# MCU_144_IOs.net
KiCad netlist of a schematic drawn in Altium Designer
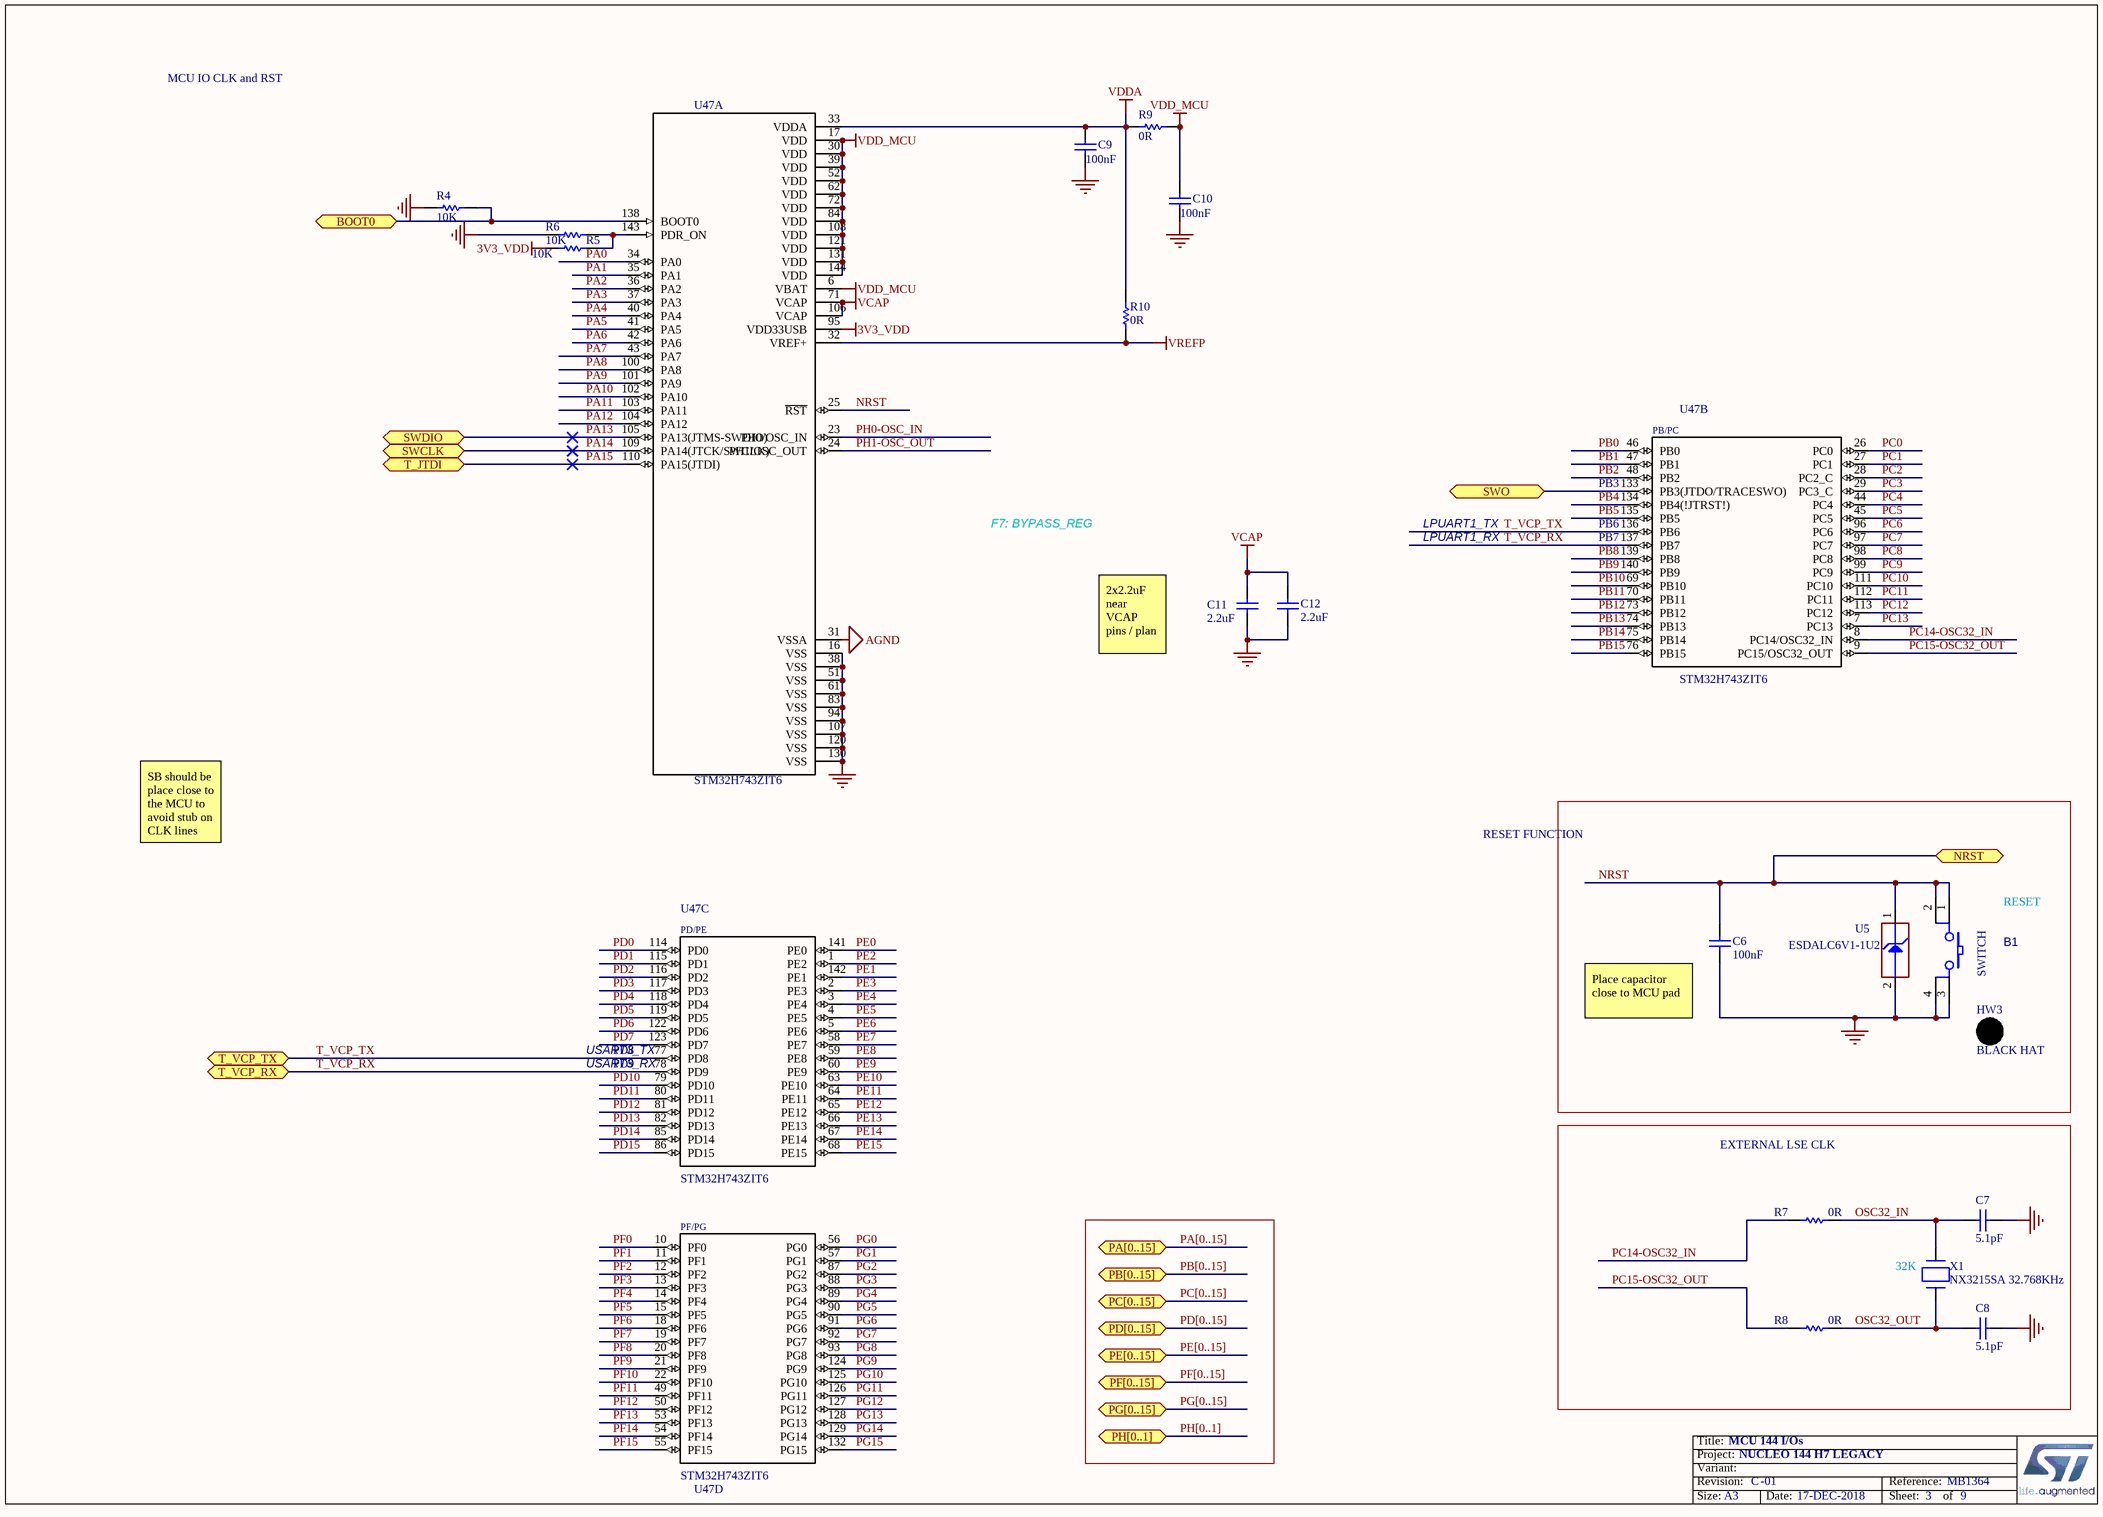
[diagram p0: MCU_144_IOs.SchDoc]

(export (version "E")
  (design (tool "Eeschema 10.0.6"))
  (components
    (comp (ref "B1")
      (value "SWITCH")
      (footprint "SWI_WEALTHMETAL_TD-0341_4P_BLACK")
      (description "Non-Open Push-Button 0.1A 24V BLACK")
      (fields
        (field (name "INTERNAL_PART_NUMBER") "MCD-00001")
        (field (name "MANUFACTURER_PART_NUMBER") "TD-0341")
        (field (name "PROVIDED_BY") "SUBCO")
      )
      (libsource (lib "MCD_PARTS_database") (part "SW-PUSH-CMS"))
    )
    (comp (ref "C6")
      (value "100nF")
      (footprint "C0603")
      (description "Capacitor, MLCC, 100nF, 6V3, X5R, 10%, 0603, T=0,8mm")
      (fields
        (field (name "INTERNAL_PART_NUMBER") "MCD-00237")
        (field (name "MANUFACTURER_PART_NUMBER") "CC0603KRX5R5BB104")
        (field (name "PROVIDED_BY") "SUBCO")
      )
      (libsource (lib "MCD_PARTS_database") (part "Capacitor"))
    )
    (comp (ref "C7")
      (value "5.1pF")
      (footprint "C0402")
      (description "Capacitor, MLCC, 5.1pF, 50V, NPO, +-0.25pF, 0402, T=0.5mm")
      (fields
        (field (name "INTERNAL_PART_NUMBER") "MCD-00003")
        (field (name "MANUFACTURER_PART_NUMBER") "CC0402CRNPO9BN5R1")
        (field (name "PROVIDED_BY") "SUBCO")
      )
      (libsource (lib "MCD_PARTS_database") (part "Capacitor"))
    )
    (comp (ref "C8")
      (value "5.1pF")
      (footprint "C0402")
      (description "Capacitor, MLCC, 5.1pF, 50V, NPO, +-0.25pF, 0402, T=0.5mm")
      (fields
        (field (name "INTERNAL_PART_NUMBER") "MCD-00003")
        (field (name "MANUFACTURER_PART_NUMBER") "CC0402CRNPO9BN5R1")
        (field (name "PROVIDED_BY") "SUBCO")
      )
      (libsource (lib "MCD_PARTS_database") (part "Capacitor"))
    )
    (comp (ref "C9")
      (value "Capacitor")
      (footprint "C0402")
      (description "CAP CER 0.1UF 16V X7R 0402")
      (fields
        (field (name "MANUFACTURER") "Yageo")
        (field (name "MANUFACTURER PART NUMBER") "CC0402KRX7R7BB104")
        (field (name "CAPACITANCE") "100nF")
      )
      (libsource (lib "MCD_PARTS_database") (part "Capacitor"))
    )
    (comp (ref "C10")
      (value "Capacitor")
      (footprint "C0402")
      (description "CAP CER 0.1UF 16V X7R 0402")
      (fields
        (field (name "MANUFACTURER") "Yageo")
        (field (name "MANUFACTURER PART NUMBER") "CC0402KRX7R7BB104")
        (field (name "CAPACITANCE") "100nF")
      )
      (libsource (lib "MCD_PARTS_database") (part "Capacitor"))
    )
    (comp (ref "C11")
      (value "2.2uF")
      (footprint "C0603")
      (description "Capacitor, MLCC, 2.2uF, 10V, X5R, 10%, 0603, T=0,8mm")
      (fields
        (field (name "INTERNAL_PART_NUMBER") "MCD-00012")
        (field (name "MANUFACTURER_PART_NUMBER") "CC0603KRX5R6BB225")
        (field (name "PROVIDED_BY") "SUBCO")
      )
      (libsource (lib "MCD_PARTS_database") (part "Capacitor"))
    )
    (comp (ref "C12")
      (value "2.2uF")
      (footprint "C0603")
      (description "Capacitor, MLCC, 2.2uF, 10V, X5R, 10%, 0603, T=0,8mm")
      (fields
        (field (name "INTERNAL_PART_NUMBER") "MCD-00012")
        (field (name "MANUFACTURER_PART_NUMBER") "CC0603KRX5R6BB225")
        (field (name "PROVIDED_BY") "SUBCO")
      )
      (libsource (lib "MCD_PARTS_database") (part "Capacitor"))
    )
    (comp (ref "HW3")
      (value "BLACK HAT")
      (description "Black Hat for switch TD0341X-G01-BLA")
      (fields
        (field (name "INTERNAL_PART_NUMBER") "MCD-00635")
        (field (name "MANUFACTURER_PART_NUMBER") "988.16.09.3.00003_SH-517")
        (field (name "PROVIDED_BY") "SUBCO")
      )
      (libsource (lib "MCD_PARTS_database") (part "BUTTON_HAT_BLACK"))
    )
    (comp (ref "R4")
      (value "10K")
      (footprint "R0603")
      (description "Resistor,10K,0603,1%,1/10W")
      (fields
        (field (name "INTERNAL_PART_NUMBER") "MCD-00220")
        (field (name "MANUFACTURER_PART_NUMBER") "RC0603FR-0710KL")
        (field (name "PROVIDED_BY") "SUBCO")
      )
      (libsource (lib "MCD_PARTS_database") (part "Resistor"))
    )
    (comp (ref "R5")
      (value "10K")
      (footprint "R0603")
      (description "Resistor,10K,0603,1%,1/10W")
      (fields
        (field (name "INTERNAL_PART_NUMBER") "MCD-00220")
        (field (name "MANUFACTURER_PART_NUMBER") "RC0603FR-0710KL")
        (field (name "PROVIDED_BY") "SUBCO")
      )
      (libsource (lib "MCD_PARTS_database") (part "Resistor"))
    )
    (comp (ref "R6")
      (value "10K")
      (footprint "R0603")
      (description "Resistor,10K,0603,1%,1/10W")
      (fields
        (field (name "INTERNAL_PART_NUMBER") "MCD-00220")
        (field (name "MANUFACTURER_PART_NUMBER") "RC0603FR-0710KL")
        (field (name "PROVIDED_BY") "SUBCO")
      )
      (libsource (lib "MCD_PARTS_database") (part "Resistor"))
    )
    (comp (ref "R7")
      (value "0R")
      (footprint "R0603")
      (description "Resistor,0R,0603,5%,1/10W")
      (fields
        (field (name "INTERNAL_PART_NUMBER") "MCD-00056")
        (field (name "MANUFACTURER_PART_NUMBER") "RC0603JR-070RL")
        (field (name "PROVIDED_BY") "SUBCO")
      )
      (libsource (lib "MCD_PARTS_database") (part "Resistor"))
    )
    (comp (ref "R8")
      (value "0R")
      (footprint "R0603")
      (description "Resistor,0R,0603,5%,1/10W")
      (fields
        (field (name "INTERNAL_PART_NUMBER") "MCD-00056")
        (field (name "MANUFACTURER_PART_NUMBER") "RC0603JR-070RL")
        (field (name "PROVIDED_BY") "SUBCO")
      )
      (libsource (lib "MCD_PARTS_database") (part "Resistor"))
    )
    (comp (ref "R9")
      (value "0R")
      (footprint "R0603")
      (description "Resistor,0R,0603,5%,1/10W")
      (fields
        (field (name "INTERNAL_PART_NUMBER") "MCD-00056")
        (field (name "MANUFACTURER_PART_NUMBER") "RC0603JR-070RL")
        (field (name "PROVIDED_BY") "SUBCO")
      )
      (libsource (lib "MCD_PARTS_database") (part "Resistor"))
    )
    (comp (ref "R10")
      (value "0R")
      (footprint "R0603")
      (description "Resistor,0R,0603,5%,1/10W")
      (fields
        (field (name "INTERNAL_PART_NUMBER") "MCD-00056")
        (field (name "MANUFACTURER_PART_NUMBER") "RC0603JR-070RL")
        (field (name "PROVIDED_BY") "SUBCO")
      )
      (libsource (lib "MCD_PARTS_database") (part "Resistor"))
    )
    (comp (ref "U5")
      (value "ESDALC6V1-1U2")
      (footprint "ESD_ST0201")
      (description "ESD protection 6V1")
      (fields
        (field (name "INTERNAL_PART_NUMBER") "MCD-00170")
        (field (name "MANUFACTURER") "STMICROELECTRONICS")
        (field (name "PROVIDED_BY") "SUBCO with ST control")
      )
      (libsource (lib "MCD_PARTS_database") (part "ESD-TRANSIL"))
    )
    (comp (ref "U47")
      (value "STM32H743ZIT6")
      (footprint "*QFP50P2200X2200X160-144N")
      (fields (field (name "MF") "STMicroelectronics") (field (name "DIGI-KEY_PART_NUMBER") "497-17721-ND"))
      (libsource (lib "STM32H743ZIT6") (part "STM32H743ZIT6"))
    )
    (comp (ref "X1")
      (value "NX3215SA 32.768KHz")
      (footprint "CRY_NX3215SA_2P")
      (description "Crystal 32.768kHz, 6pF, +-20ppm, 50Kohms max, SMD")
      (fields
        (field (name "INTERNAL_PART_NUMBER") "MCD-00091")
        (field (name "MANUFACTURER_PART_NUMBER") "NX3215SA 32.768KHz EXS00A-MU00525")
        (field (name "PROVIDED_BY") "SUBCO")
      )
      (libsource (lib "MCD_PARTS_database") (part "XTAL_2_PINS"))
    )
  )
  (nets
    (net (code "10") (name "/BOOT0") (class "Default")
      (node (ref "R4") (pin "1") (pinfunction "1_1") (pintype "passive"))
      (node (ref "U47") (pin "138") (pinfunction "BOOT0_138") (pintype "input"))
    )
    (net (code "11") (name "/NRST") (class "Default")
      (node (ref "B1") (pin "1") (pinfunction "1_1") (pintype "passive"))
      (node (ref "B1") (pin "2") (pinfunction "2_2") (pintype "passive"))
      (node (ref "C6") (pin "2") (pinfunction "2_2") (pintype "passive"))
      (node (ref "U47") (pin "25") (pinfunction "~{RST}_25") (pintype "bidirectional"))
      (node (ref "U5") (pin "1") (pinfunction "IO1_1") (pintype "passive"))
    )
    (net (code "12") (name "/OSC32_IN") (class "Default")
      (node (ref "C7") (pin "1") (pinfunction "1_1") (pintype "passive"))
      (node (ref "R7") (pin "2") (pinfunction "2_2") (pintype "passive"))
      (node (ref "X1") (pin "2") (pinfunction "X2_2") (pintype "passive"))
    )
    (net (code "13") (name "/OSC32_OUT") (class "Default")
      (node (ref "C8") (pin "1") (pinfunction "1_1") (pintype "passive"))
      (node (ref "R8") (pin "2") (pinfunction "2_2") (pintype "passive"))
      (node (ref "X1") (pin "1") (pinfunction "X1_1") (pintype "passive"))
    )
    (net (code "14") (name "/PA0") (class "Default")
      (node (ref "U47") (pin "34") (pinfunction "PA0_34") (pintype "bidirectional"))
    )
    (net (code "15") (name "/PA1") (class "Default")
      (node (ref "U47") (pin "35") (pinfunction "PA1_35") (pintype "bidirectional"))
    )
    (net (code "16") (name "/PA2") (class "Default")
      (node (ref "U47") (pin "36") (pinfunction "PA2_36") (pintype "bidirectional"))
    )
    (net (code "17") (name "/PA3") (class "Default")
      (node (ref "U47") (pin "37") (pinfunction "PA3_37") (pintype "bidirectional"))
    )
    (net (code "18") (name "/PA4") (class "Default")
      (node (ref "U47") (pin "40") (pinfunction "PA4_40") (pintype "bidirectional"))
    )
    (net (code "19") (name "/PA5") (class "Default")
      (node (ref "U47") (pin "41") (pinfunction "PA5_41") (pintype "bidirectional"))
    )
    (net (code "20") (name "/PA6") (class "Default")
      (node (ref "U47") (pin "42") (pinfunction "PA6_42") (pintype "bidirectional"))
    )
    (net (code "21") (name "/PA7") (class "Default")
      (node (ref "U47") (pin "43") (pinfunction "PA7_43") (pintype "bidirectional"))
    )
    (net (code "22") (name "/PA8") (class "Default")
      (node (ref "U47") (pin "100") (pinfunction "PA8_100") (pintype "bidirectional"))
    )
    (net (code "23") (name "/PA9") (class "Default")
      (node (ref "U47") (pin "101") (pinfunction "PA9_101") (pintype "bidirectional"))
    )
    (net (code "24") (name "/PA10") (class "Default")
      (node (ref "U47") (pin "102") (pinfunction "PA10_102") (pintype "bidirectional"))
    )
    (net (code "25") (name "/PA11") (class "Default")
      (node (ref "U47") (pin "103") (pinfunction "PA11_103") (pintype "bidirectional"))
    )
    (net (code "26") (name "/PA12") (class "Default")
      (node (ref "U47") (pin "104") (pinfunction "PA12_104") (pintype "bidirectional"))
    )
    (net (code "27") (name "/PA13") (class "Default")
      (node (ref "U47") (pin "105") (pinfunction "PA13(JTMS-SWDIO)_105") (pintype "bidirectional"))
    )
    (net (code "28") (name "/PA14") (class "Default")
      (node (ref "U47") (pin "109") (pinfunction "PA14(JTCK/SWCLK)_109") (pintype "bidirectional"))
    )
    (net (code "29") (name "/PA15") (class "Default")
      (node (ref "U47") (pin "110") (pinfunction "PA15(JTDI)_110") (pintype "bidirectional"))
    )
    (net (code "31") (name "/PB0") (class "Default")
      (node (ref "U47") (pin "46") (pinfunction "PB0_46") (pintype "bidirectional"))
    )
    (net (code "32") (name "/PB1") (class "Default")
      (node (ref "U47") (pin "47") (pinfunction "PB1_47") (pintype "bidirectional"))
    )
    (net (code "33") (name "/PB2") (class "Default")
      (node (ref "U47") (pin "48") (pinfunction "PB2_48") (pintype "bidirectional"))
    )
    (net (code "34") (name "/PB4") (class "Default")
      (node (ref "U47") (pin "134") (pinfunction "PB4(!JTRST!)_134") (pintype "bidirectional"))
    )
    (net (code "35") (name "/PB5") (class "Default")
      (node (ref "U47") (pin "135") (pinfunction "PB5_135") (pintype "bidirectional"))
    )
    (net (code "36") (name "/PB8") (class "Default")
      (node (ref "U47") (pin "139") (pinfunction "PB8_139") (pintype "bidirectional"))
    )
    (net (code "37") (name "/PB9") (class "Default")
      (node (ref "U47") (pin "140") (pinfunction "PB9_140") (pintype "bidirectional"))
    )
    (net (code "38") (name "/PB10") (class "Default")
      (node (ref "U47") (pin "69") (pinfunction "PB10_69") (pintype "bidirectional"))
    )
    (net (code "39") (name "/PB11") (class "Default")
      (node (ref "U47") (pin "70") (pinfunction "PB11_70") (pintype "bidirectional"))
    )
    (net (code "40") (name "/PB12") (class "Default")
      (node (ref "U47") (pin "73") (pinfunction "PB12_73") (pintype "bidirectional"))
    )
    (net (code "41") (name "/PB13") (class "Default")
      (node (ref "U47") (pin "74") (pinfunction "PB13_74") (pintype "bidirectional"))
    )
    (net (code "42") (name "/PB14") (class "Default")
      (node (ref "U47") (pin "75") (pinfunction "PB14_75") (pintype "bidirectional"))
    )
    (net (code "43") (name "/PB15") (class "Default")
      (node (ref "U47") (pin "76") (pinfunction "PB15_76") (pintype "bidirectional"))
    )
    (net (code "45") (name "/PC0") (class "Default")
      (node (ref "U47") (pin "26") (pinfunction "PC0_26") (pintype "bidirectional"))
    )
    (net (code "46") (name "/PC1") (class "Default")
      (node (ref "U47") (pin "27") (pinfunction "PC1_27") (pintype "bidirectional"))
    )
    (net (code "47") (name "/PC2") (class "Default")
      (node (ref "U47") (pin "28") (pinfunction "PC2_C_28") (pintype "bidirectional"))
    )
    (net (code "48") (name "/PC3") (class "Default")
      (node (ref "U47") (pin "29") (pinfunction "PC3_C_29") (pintype "bidirectional"))
    )
    (net (code "49") (name "/PC4") (class "Default")
      (node (ref "U47") (pin "44") (pinfunction "PC4_44") (pintype "bidirectional"))
    )
    (net (code "50") (name "/PC5") (class "Default")
      (node (ref "U47") (pin "45") (pinfunction "PC5_45") (pintype "bidirectional"))
    )
    (net (code "51") (name "/PC6") (class "Default")
      (node (ref "U47") (pin "96") (pinfunction "PC6_96") (pintype "bidirectional"))
    )
    (net (code "52") (name "/PC7") (class "Default")
      (node (ref "U47") (pin "97") (pinfunction "PC7_97") (pintype "bidirectional"))
    )
    (net (code "53") (name "/PC8") (class "Default")
      (node (ref "U47") (pin "98") (pinfunction "PC8_98") (pintype "bidirectional"))
    )
    (net (code "54") (name "/PC9") (class "Default")
      (node (ref "U47") (pin "99") (pinfunction "PC9_99") (pintype "bidirectional"))
    )
    (net (code "55") (name "/PC10") (class "Default")
      (node (ref "U47") (pin "111") (pinfunction "PC10_111") (pintype "bidirectional"))
    )
    (net (code "56") (name "/PC11") (class "Default")
      (node (ref "U47") (pin "112") (pinfunction "PC11_112") (pintype "bidirectional"))
    )
    (net (code "57") (name "/PC12") (class "Default")
      (node (ref "U47") (pin "113") (pinfunction "PC12_113") (pintype "bidirectional"))
    )
    (net (code "58") (name "/PC13") (class "Default")
      (node (ref "U47") (pin "7") (pinfunction "PC13_7") (pintype "bidirectional"))
    )
    (net (code "59") (name "/PC14-OSC32_IN") (class "Default")
      (node (ref "R7") (pin "1") (pinfunction "1_1") (pintype "passive"))
      (node (ref "U47") (pin "8") (pinfunction "PC14/OSC32_IN_8") (pintype "bidirectional"))
    )
    (net (code "60") (name "/PC15-OSC32_OUT") (class "Default")
      (node (ref "R8") (pin "1") (pinfunction "1_1") (pintype "passive"))
      (node (ref "U47") (pin "9") (pinfunction "PC15/OSC32_OUT_9") (pintype "bidirectional"))
    )
    (net (code "62") (name "/PD0") (class "Default")
      (node (ref "U47") (pin "114") (pinfunction "PD0_114") (pintype "bidirectional"))
    )
    (net (code "63") (name "/PD1") (class "Default")
      (node (ref "U47") (pin "115") (pinfunction "PD1_115") (pintype "bidirectional"))
    )
    (net (code "64") (name "/PD2") (class "Default")
      (node (ref "U47") (pin "116") (pinfunction "PD2_116") (pintype "bidirectional"))
    )
    (net (code "65") (name "/PD3") (class "Default")
      (node (ref "U47") (pin "117") (pinfunction "PD3_117") (pintype "bidirectional"))
    )
    (net (code "66") (name "/PD4") (class "Default")
      (node (ref "U47") (pin "118") (pinfunction "PD4_118") (pintype "bidirectional"))
    )
    (net (code "67") (name "/PD5") (class "Default")
      (node (ref "U47") (pin "119") (pinfunction "PD5_119") (pintype "bidirectional"))
    )
    (net (code "68") (name "/PD6") (class "Default")
      (node (ref "U47") (pin "122") (pinfunction "PD6_122") (pintype "bidirectional"))
    )
    (net (code "69") (name "/PD7") (class "Default")
      (node (ref "U47") (pin "123") (pinfunction "PD7_123") (pintype "bidirectional"))
    )
    (net (code "70") (name "/PD10") (class "Default")
      (node (ref "U47") (pin "79") (pinfunction "PD10_79") (pintype "bidirectional"))
    )
    (net (code "71") (name "/PD11") (class "Default")
      (node (ref "U47") (pin "80") (pinfunction "PD11_80") (pintype "bidirectional"))
    )
    (net (code "72") (name "/PD12") (class "Default")
      (node (ref "U47") (pin "81") (pinfunction "PD12_81") (pintype "bidirectional"))
    )
    (net (code "73") (name "/PD13") (class "Default")
      (node (ref "U47") (pin "82") (pinfunction "PD13_82") (pintype "bidirectional"))
    )
    (net (code "74") (name "/PD14") (class "Default")
      (node (ref "U47") (pin "85") (pinfunction "PD14_85") (pintype "bidirectional"))
    )
    (net (code "75") (name "/PD15") (class "Default")
      (node (ref "U47") (pin "86") (pinfunction "PD15_86") (pintype "bidirectional"))
    )
    (net (code "77") (name "/PE0") (class "Default")
      (node (ref "U47") (pin "141") (pinfunction "PE0_141") (pintype "bidirectional"))
    )
    (net (code "78") (name "/PE1") (class "Default")
      (node (ref "U47") (pin "142") (pinfunction "PE1_142") (pintype "bidirectional"))
    )
    (net (code "79") (name "/PE2") (class "Default")
      (node (ref "U47") (pin "1") (pinfunction "PE2_1") (pintype "bidirectional"))
    )
    (net (code "80") (name "/PE3") (class "Default")
      (node (ref "U47") (pin "2") (pinfunction "PE3_2") (pintype "bidirectional"))
    )
    (net (code "81") (name "/PE4") (class "Default")
      (node (ref "U47") (pin "3") (pinfunction "PE4_3") (pintype "bidirectional"))
    )
    (net (code "82") (name "/PE5") (class "Default")
      (node (ref "U47") (pin "4") (pinfunction "PE5_4") (pintype "bidirectional"))
    )
    (net (code "83") (name "/PE6") (class "Default")
      (node (ref "U47") (pin "5") (pinfunction "PE6_5") (pintype "bidirectional"))
    )
    (net (code "84") (name "/PE7") (class "Default")
      (node (ref "U47") (pin "58") (pinfunction "PE7_58") (pintype "bidirectional"))
    )
    (net (code "85") (name "/PE8") (class "Default")
      (node (ref "U47") (pin "59") (pinfunction "PE8_59") (pintype "bidirectional"))
    )
    (net (code "86") (name "/PE9") (class "Default")
      (node (ref "U47") (pin "60") (pinfunction "PE9_60") (pintype "bidirectional"))
    )
    (net (code "87") (name "/PE10") (class "Default")
      (node (ref "U47") (pin "63") (pinfunction "PE10_63") (pintype "bidirectional"))
    )
    (net (code "88") (name "/PE11") (class "Default")
      (node (ref "U47") (pin "64") (pinfunction "PE11_64") (pintype "bidirectional"))
    )
    (net (code "89") (name "/PE12") (class "Default")
      (node (ref "U47") (pin "65") (pinfunction "PE12_65") (pintype "bidirectional"))
    )
    (net (code "90") (name "/PE13") (class "Default")
      (node (ref "U47") (pin "66") (pinfunction "PE13_66") (pintype "bidirectional"))
    )
    (net (code "91") (name "/PE14") (class "Default")
      (node (ref "U47") (pin "67") (pinfunction "PE14_67") (pintype "bidirectional"))
    )
    (net (code "92") (name "/PE15") (class "Default")
      (node (ref "U47") (pin "68") (pinfunction "PE15_68") (pintype "bidirectional"))
    )
    (net (code "94") (name "/PF0") (class "Default")
      (node (ref "U47") (pin "10") (pinfunction "PF0_10") (pintype "bidirectional"))
    )
    (net (code "95") (name "/PF1") (class "Default")
      (node (ref "U47") (pin "11") (pinfunction "PF1_11") (pintype "bidirectional"))
    )
    (net (code "96") (name "/PF2") (class "Default")
      (node (ref "U47") (pin "12") (pinfunction "PF2_12") (pintype "bidirectional"))
    )
    (net (code "97") (name "/PF3") (class "Default")
      (node (ref "U47") (pin "13") (pinfunction "PF3_13") (pintype "bidirectional"))
    )
    (net (code "98") (name "/PF4") (class "Default")
      (node (ref "U47") (pin "14") (pinfunction "PF4_14") (pintype "bidirectional"))
    )
    (net (code "99") (name "/PF5") (class "Default")
      (node (ref "U47") (pin "15") (pinfunction "PF5_15") (pintype "bidirectional"))
    )
    (net (code "100") (name "/PF6") (class "Default")
      (node (ref "U47") (pin "18") (pinfunction "PF6_18") (pintype "bidirectional"))
    )
    (net (code "101") (name "/PF7") (class "Default")
      (node (ref "U47") (pin "19") (pinfunction "PF7_19") (pintype "bidirectional"))
    )
    (net (code "102") (name "/PF8") (class "Default")
      (node (ref "U47") (pin "20") (pinfunction "PF8_20") (pintype "bidirectional"))
    )
    (net (code "103") (name "/PF9") (class "Default")
      (node (ref "U47") (pin "21") (pinfunction "PF9_21") (pintype "bidirectional"))
    )
    (net (code "104") (name "/PF10") (class "Default")
      (node (ref "U47") (pin "22") (pinfunction "PF10_22") (pintype "bidirectional"))
    )
    (net (code "105") (name "/PF11") (class "Default")
      (node (ref "U47") (pin "49") (pinfunction "PF11_49") (pintype "bidirectional"))
    )
    (net (code "106") (name "/PF12") (class "Default")
      (node (ref "U47") (pin "50") (pinfunction "PF12_50") (pintype "bidirectional"))
    )
    (net (code "107") (name "/PF13") (class "Default")
      (node (ref "U47") (pin "53") (pinfunction "PF13_53") (pintype "bidirectional"))
    )
    (net (code "108") (name "/PF14") (class "Default")
      (node (ref "U47") (pin "54") (pinfunction "PF14_54") (pintype "bidirectional"))
    )
    (net (code "109") (name "/PF15") (class "Default")
      (node (ref "U47") (pin "55") (pinfunction "PF15_55") (pintype "bidirectional"))
    )
    (net (code "111") (name "/PG0") (class "Default")
      (node (ref "U47") (pin "56") (pinfunction "PG0_56") (pintype "bidirectional"))
    )
    (net (code "112") (name "/PG1") (class "Default")
      (node (ref "U47") (pin "57") (pinfunction "PG1_57") (pintype "bidirectional"))
    )
    (net (code "113") (name "/PG2") (class "Default")
      (node (ref "U47") (pin "87") (pinfunction "PG2_87") (pintype "bidirectional"))
    )
    (net (code "114") (name "/PG3") (class "Default")
      (node (ref "U47") (pin "88") (pinfunction "PG3_88") (pintype "bidirectional"))
    )
    (net (code "115") (name "/PG4") (class "Default")
      (node (ref "U47") (pin "89") (pinfunction "PG4_89") (pintype "bidirectional"))
    )
    (net (code "116") (name "/PG5") (class "Default")
      (node (ref "U47") (pin "90") (pinfunction "PG5_90") (pintype "bidirectional"))
    )
    (net (code "117") (name "/PG6") (class "Default")
      (node (ref "U47") (pin "91") (pinfunction "PG6_91") (pintype "bidirectional"))
    )
    (net (code "118") (name "/PG7") (class "Default")
      (node (ref "U47") (pin "92") (pinfunction "PG7_92") (pintype "bidirectional"))
    )
    (net (code "119") (name "/PG8") (class "Default")
      (node (ref "U47") (pin "93") (pinfunction "PG8_93") (pintype "bidirectional"))
    )
    (net (code "120") (name "/PG9") (class "Default")
      (node (ref "U47") (pin "124") (pinfunction "PG9_124") (pintype "bidirectional"))
    )
    (net (code "121") (name "/PG10") (class "Default")
      (node (ref "U47") (pin "125") (pinfunction "PG10_125") (pintype "bidirectional"))
    )
    (net (code "122") (name "/PG11") (class "Default")
      (node (ref "U47") (pin "126") (pinfunction "PG11_126") (pintype "bidirectional"))
    )
    (net (code "123") (name "/PG12") (class "Default")
      (node (ref "U47") (pin "127") (pinfunction "PG12_127") (pintype "bidirectional"))
    )
    (net (code "124") (name "/PG13") (class "Default")
      (node (ref "U47") (pin "128") (pinfunction "PG13_128") (pintype "bidirectional"))
    )
    (net (code "125") (name "/PG14") (class "Default")
      (node (ref "U47") (pin "129") (pinfunction "PG14_129") (pintype "bidirectional"))
    )
    (net (code "126") (name "/PG15") (class "Default")
      (node (ref "U47") (pin "132") (pinfunction "PG15_132") (pintype "bidirectional"))
    )
    (net (code "128") (name "/PH0-OSC_IN") (class "Default")
      (node (ref "U47") (pin "23") (pinfunction "PH0/OSC_IN_23") (pintype "bidirectional"))
    )
    (net (code "129") (name "/PH1-OSC_OUT") (class "Default")
      (node (ref "U47") (pin "24") (pinfunction "PH1/OSC_OUT_24") (pintype "bidirectional"))
    )
    (net (code "131") (name "/SWO") (class "Default")
      (node (ref "U47") (pin "133") (pinfunction "PB3(JTDO/TRACESWO)_133") (pintype "bidirectional"))
    )
    (net (code "132") (name "/T_VCP_RX") (class "Default")
      (node (ref "U47") (pin "137") (pinfunction "PB7_137") (pintype "bidirectional"))
      (node (ref "U47") (pin "78") (pinfunction "PD9_78") (pintype "bidirectional"))
    )
    (net (code "133") (name "/T_VCP_TX") (class "Default")
      (node (ref "U47") (pin "136") (pinfunction "PB6_136") (pintype "bidirectional"))
      (node (ref "U47") (pin "77") (pinfunction "PD8_77") (pintype "bidirectional"))
    )
    (net (code "134") (name "3V3_VDD") (class "Default")
      (node (ref "R5") (pin "2") (pinfunction "2_2") (pintype "passive"))
      (node (ref "U47") (pin "95") (pinfunction "VDD33USB_95") (pintype "power_in"))
    )
    (net (code "135") (name "AGND") (class "Default")
      (node (ref "U47") (pin "31") (pinfunction "VSSA_31") (pintype "power_in"))
    )
    (net (code "136") (name "GND") (class "Default")
      (node (ref "B1") (pin "3") (pinfunction "3_3") (pintype "passive"))
      (node (ref "B1") (pin "4") (pinfunction "4_4") (pintype "passive"))
      (node (ref "C10") (pin "1") (pinfunction "1_1") (pintype "passive"))
      (node (ref "C11") (pin "1") (pinfunction "1_1") (pintype "passive"))
      (node (ref "C12") (pin "1") (pinfunction "1_1") (pintype "passive"))
      (node (ref "C6") (pin "1") (pinfunction "1_1") (pintype "passive"))
      (node (ref "C7") (pin "2") (pinfunction "2_2") (pintype "passive"))
      (node (ref "C8") (pin "2") (pinfunction "2_2") (pintype "passive"))
      (node (ref "C9") (pin "1") (pinfunction "1_1") (pintype "passive"))
      (node (ref "R4") (pin "2") (pinfunction "2_2") (pintype "passive"))
      (node (ref "R6") (pin "2") (pinfunction "2_2") (pintype "passive"))
      (node (ref "U47") (pin "107") (pinfunction "VSS_107") (pintype "power_in"))
      (node (ref "U47") (pin "120") (pinfunction "VSS_120") (pintype "power_in"))
      (node (ref "U47") (pin "130") (pinfunction "VSS_130") (pintype "power_in"))
      (node (ref "U47") (pin "16") (pinfunction "VSS_16") (pintype "power_in"))
      (node (ref "U47") (pin "38") (pinfunction "VSS_38") (pintype "power_in"))
      (node (ref "U47") (pin "51") (pinfunction "VSS_51") (pintype "power_in"))
      (node (ref "U47") (pin "61") (pinfunction "VSS_61") (pintype "power_in"))
      (node (ref "U47") (pin "83") (pinfunction "VSS_83") (pintype "power_in"))
      (node (ref "U47") (pin "94") (pinfunction "VSS_94") (pintype "power_in"))
      (node (ref "U5") (pin "2") (pinfunction "GND_2") (pintype "passive"))
    )
    (net (code "137") (name "Net-(U47A-PDR_ON)") (class "Default")
      (node (ref "R5") (pin "1") (pinfunction "1_1") (pintype "passive"))
      (node (ref "R6") (pin "1") (pinfunction "1_1") (pintype "passive"))
      (node (ref "U47") (pin "143") (pinfunction "PDR_ON_143") (pintype "input"))
    )
    (net (code "138") (name "VCAP") (class "Default")
      (node (ref "C11") (pin "2") (pinfunction "2_2") (pintype "passive"))
      (node (ref "C12") (pin "2") (pinfunction "2_2") (pintype "passive"))
      (node (ref "U47") (pin "106") (pinfunction "VCAP_106") (pintype "power_in"))
      (node (ref "U47") (pin "71") (pinfunction "VCAP_71") (pintype "power_in"))
    )
    (net (code "139") (name "VDDA") (class "Default")
      (node (ref "C9") (pin "2") (pinfunction "2_2") (pintype "passive"))
      (node (ref "R10") (pin "1") (pinfunction "1_1") (pintype "passive"))
      (node (ref "R9") (pin "1") (pinfunction "1_1") (pintype "passive"))
      (node (ref "U47") (pin "33") (pinfunction "VDDA_33") (pintype "power_in"))
    )
    (net (code "140") (name "VDD_MCU") (class "Default")
      (node (ref "C10") (pin "2") (pinfunction "2_2") (pintype "passive"))
      (node (ref "R9") (pin "2") (pinfunction "2_2") (pintype "passive"))
      (node (ref "U47") (pin "108") (pinfunction "VDD_108") (pintype "power_in"))
      (node (ref "U47") (pin "121") (pinfunction "VDD_121") (pintype "power_in"))
      (node (ref "U47") (pin "131") (pinfunction "VDD_131") (pintype "power_in"))
      (node (ref "U47") (pin "144") (pinfunction "VDD_144") (pintype "power_in"))
      (node (ref "U47") (pin "17") (pinfunction "VDD_17") (pintype "power_in"))
      (node (ref "U47") (pin "30") (pinfunction "VDD_30") (pintype "power_in"))
      (node (ref "U47") (pin "39") (pinfunction "VDD_39") (pintype "power_in"))
      (node (ref "U47") (pin "52") (pinfunction "VDD_52") (pintype "power_in"))
      (node (ref "U47") (pin "6") (pinfunction "VBAT_6") (pintype "power_in"))
      (node (ref "U47") (pin "62") (pinfunction "VDD_62") (pintype "power_in"))
      (node (ref "U47") (pin "72") (pinfunction "VDD_72") (pintype "power_in"))
      (node (ref "U47") (pin "84") (pinfunction "VDD_84") (pintype "power_in"))
    )
    (net (code "141") (name "VREFP") (class "Default")
      (node (ref "R10") (pin "2") (pinfunction "2_2") (pintype "passive"))
      (node (ref "U47") (pin "32") (pinfunction "VREF+_32") (pintype "power_in"))
    )
  )
)
